# Sheet1.net
KiCad netlist of a schematic drawn in Altium Designer
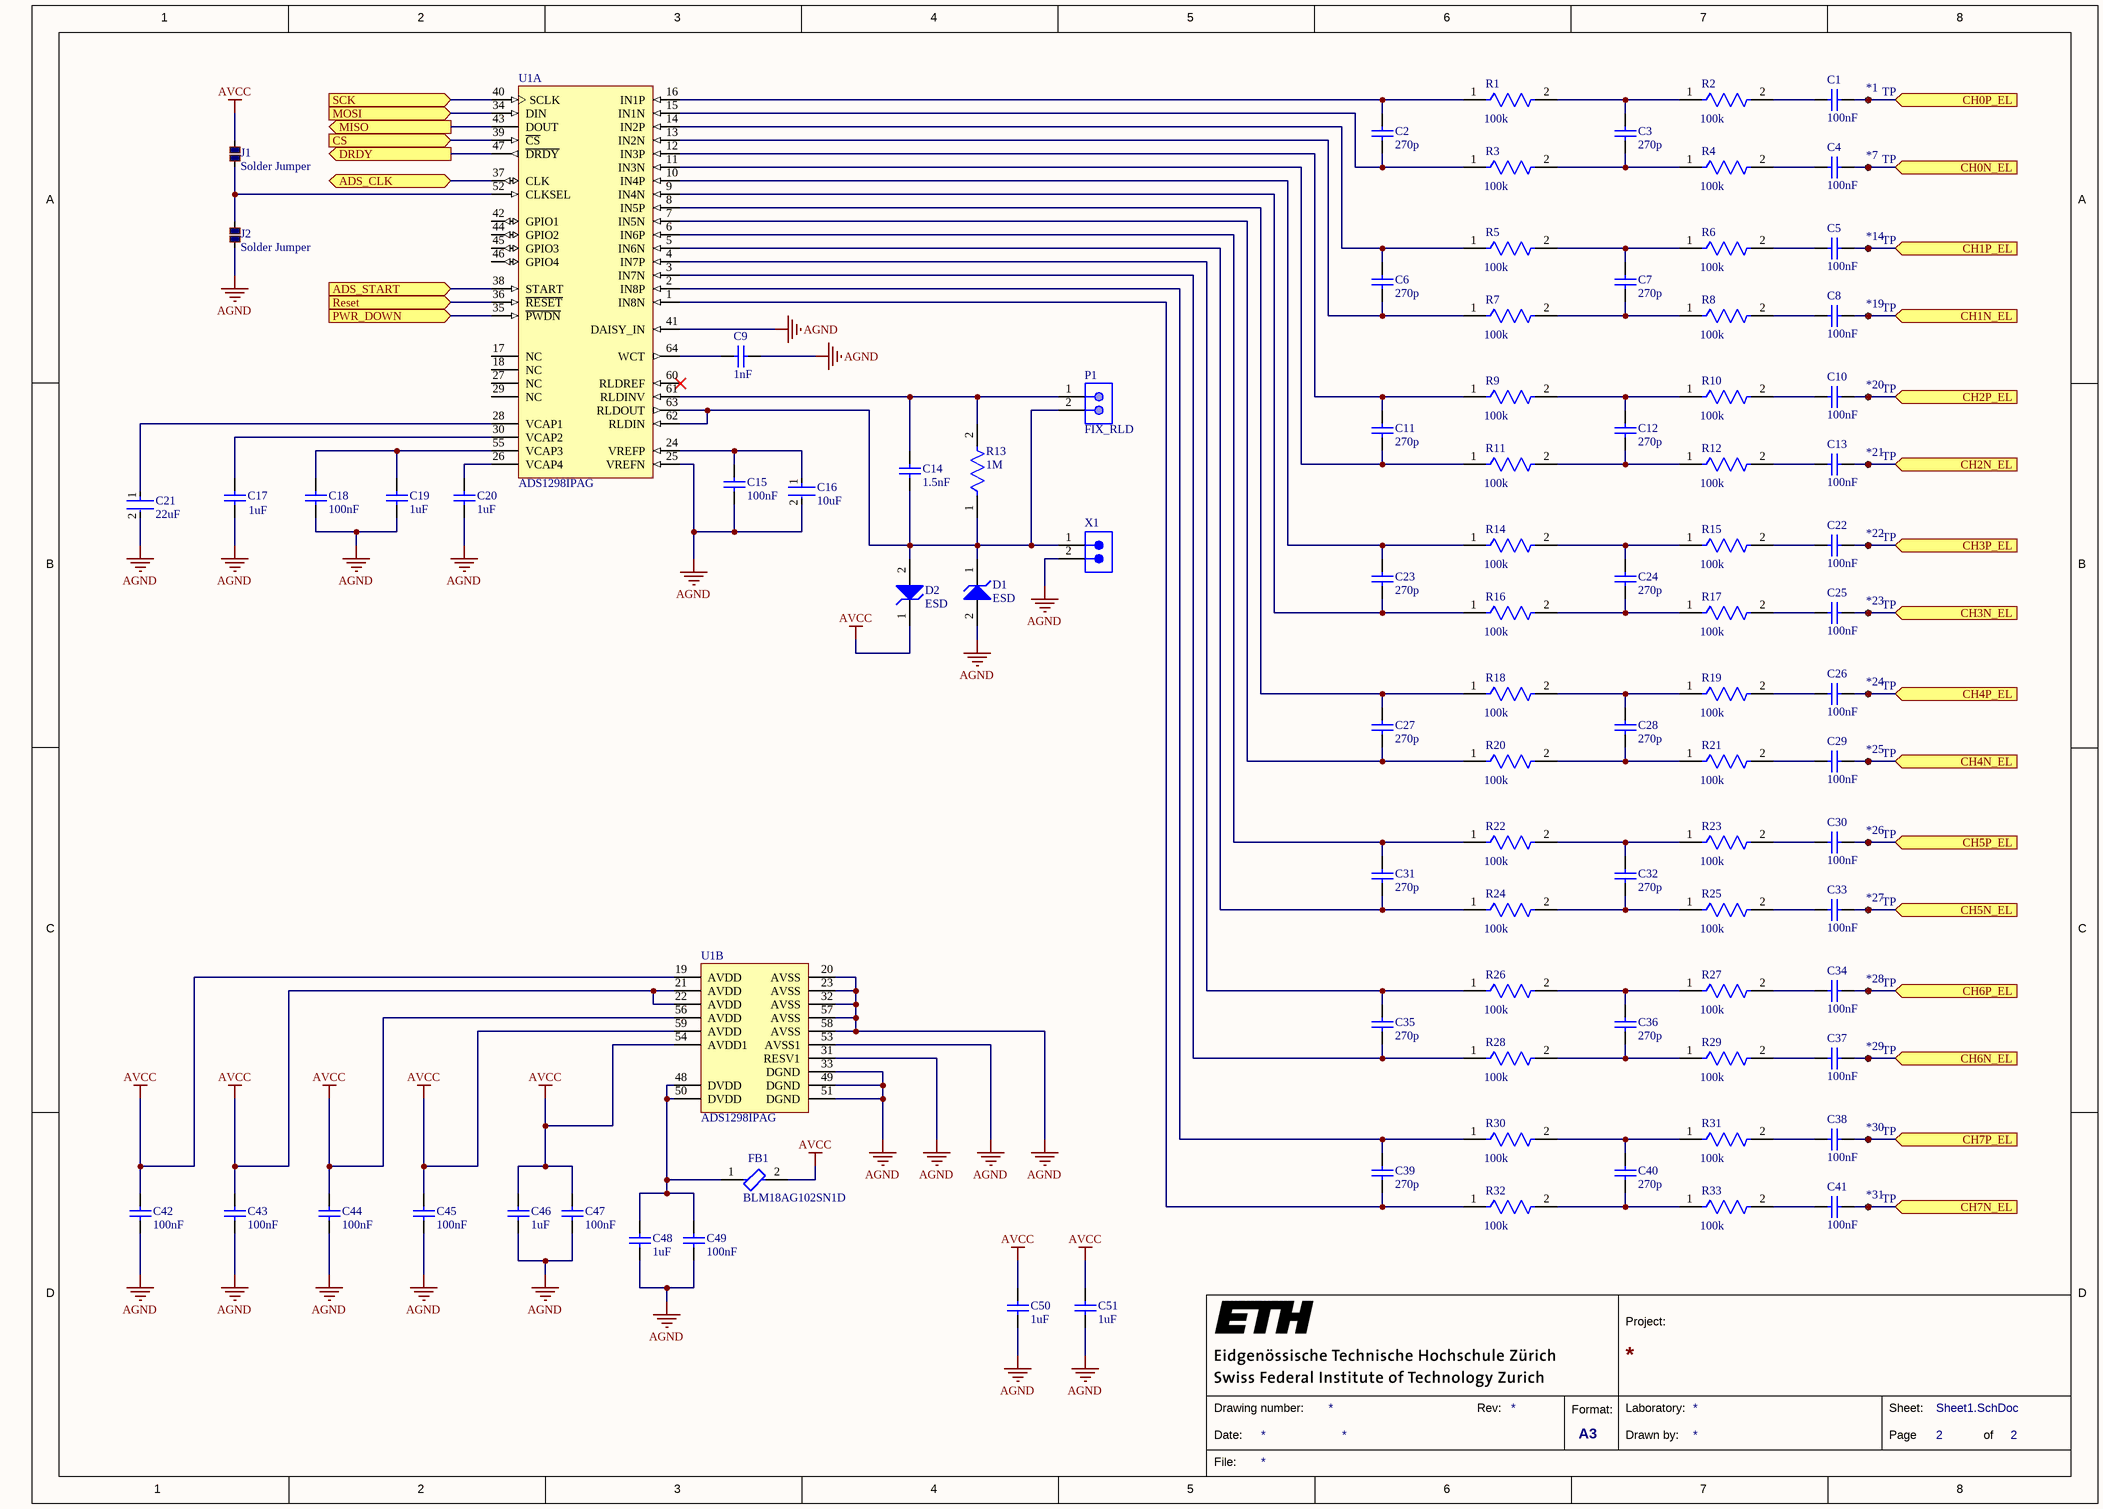
[diagram p0: Sheet1.SchDoc]

(export (version "E")
  (design (tool "Eeschema 10.0.6"))
  (components
    (comp (ref "*1")
      (value "TP")
      (footprint "Pad-1mm")
      (description "1mm SMT Test Pad")
      (libsource (lib "ETHZ Vault") (part "Test Pad"))
    )
    (comp (ref "*7")
      (value "TP")
      (footprint "Pad-1mm")
      (description "1mm SMT Test Pad")
      (libsource (lib "ETHZ Vault") (part "Test Pad"))
    )
    (comp (ref "*14")
      (value "TP")
      (footprint "Pad-1mm")
      (description "1mm SMT Test Pad")
      (libsource (lib "ETHZ Vault") (part "Test Pad"))
    )
    (comp (ref "*19")
      (value "TP")
      (footprint "Pad-1mm")
      (description "1mm SMT Test Pad")
      (libsource (lib "ETHZ Vault") (part "Test Pad"))
    )
    (comp (ref "*20")
      (value "TP")
      (footprint "Pad-1mm")
      (description "1mm SMT Test Pad")
      (libsource (lib "ETHZ Vault") (part "Test Pad"))
    )
    (comp (ref "*21")
      (value "TP")
      (footprint "Pad-1mm")
      (description "1mm SMT Test Pad")
      (libsource (lib "ETHZ Vault") (part "Test Pad"))
    )
    (comp (ref "*22")
      (value "TP")
      (footprint "Pad-1mm")
      (description "1mm SMT Test Pad")
      (libsource (lib "ETHZ Vault") (part "Test Pad"))
    )
    (comp (ref "*23")
      (value "TP")
      (footprint "Pad-1mm")
      (description "1mm SMT Test Pad")
      (libsource (lib "ETHZ Vault") (part "Test Pad"))
    )
    (comp (ref "*24")
      (value "TP")
      (footprint "Pad-1mm")
      (description "1mm SMT Test Pad")
      (libsource (lib "ETHZ Vault") (part "Test Pad"))
    )
    (comp (ref "*25")
      (value "TP")
      (footprint "Pad-1mm")
      (description "1mm SMT Test Pad")
      (libsource (lib "ETHZ Vault") (part "Test Pad"))
    )
    (comp (ref "*26")
      (value "TP")
      (footprint "Pad-1mm")
      (description "1mm SMT Test Pad")
      (libsource (lib "ETHZ Vault") (part "Test Pad"))
    )
    (comp (ref "*27")
      (value "TP")
      (footprint "Pad-1mm")
      (description "1mm SMT Test Pad")
      (libsource (lib "ETHZ Vault") (part "Test Pad"))
    )
    (comp (ref "*28")
      (value "TP")
      (footprint "Pad-1mm")
      (description "1mm SMT Test Pad")
      (libsource (lib "ETHZ Vault") (part "Test Pad"))
    )
    (comp (ref "*29")
      (value "TP")
      (footprint "Pad-1mm")
      (description "1mm SMT Test Pad")
      (libsource (lib "ETHZ Vault") (part "Test Pad"))
    )
    (comp (ref "*30")
      (value "TP")
      (footprint "Pad-1mm")
      (description "1mm SMT Test Pad")
      (libsource (lib "ETHZ Vault") (part "Test Pad"))
    )
    (comp (ref "*31")
      (value "TP")
      (footprint "Pad-1mm")
      (description "1mm SMT Test Pad")
      (libsource (lib "ETHZ Vault") (part "Test Pad"))
    )
    (comp (ref "C1")
      (value "100nF")
      (footprint "CAPC1608X92X38LL15T08")
      (fields (field (name "MANUFACTURER") "Vitramon") (field (name "PART NUMBER") "VJ0603Y104JXJAC"))
      (libsource (lib "Altium Content Vault") (part "CAP"))
    )
    (comp (ref "C2")
      (value "270p")
      (footprint "CAPC1608X90X35NL10T15")
      (fields (field (name "MANUFACTURER") "Murata") (field (name "PART NUMBER") "GCM1885C1H271JA16D"))
      (libsource (lib "Altium Content Vault") (part "CAP"))
    )
    (comp (ref "C3")
      (value "270p")
      (footprint "CAPC1608X90X35NL10T15")
      (fields (field (name "MANUFACTURER") "Murata") (field (name "PART NUMBER") "GCM1885C1H271JA16D"))
      (libsource (lib "Altium Content Vault") (part "CAP"))
    )
    (comp (ref "C4")
      (value "100nF")
      (footprint "CAPC1608X92X38LL15T08")
      (fields (field (name "MANUFACTURER") "Vitramon") (field (name "PART NUMBER") "VJ0603Y104JXJAC"))
      (libsource (lib "Altium Content Vault") (part "CAP"))
    )
    (comp (ref "C5")
      (value "100nF")
      (footprint "CAPC1608X92X38LL15T08")
      (fields (field (name "MANUFACTURER") "Vitramon") (field (name "PART NUMBER") "VJ0603Y104JXJAC"))
      (libsource (lib "Altium Content Vault") (part "CAP"))
    )
    (comp (ref "C6")
      (value "270p")
      (footprint "CAPC1608X90X35NL10T15")
      (fields (field (name "MANUFACTURER") "Murata") (field (name "PART NUMBER") "GCM1885C1H271JA16D"))
      (libsource (lib "Altium Content Vault") (part "CAP"))
    )
    (comp (ref "C7")
      (value "270p")
      (footprint "CAPC1608X90X35NL10T15")
      (fields (field (name "MANUFACTURER") "Murata") (field (name "PART NUMBER") "GCM1885C1H271JA16D"))
      (libsource (lib "Altium Content Vault") (part "CAP"))
    )
    (comp (ref "C8")
      (value "100nF")
      (footprint "CAPC1608X92X38LL15T08")
      (fields (field (name "MANUFACTURER") "Vitramon") (field (name "PART NUMBER") "VJ0603Y104JXJAC"))
      (libsource (lib "Altium Content Vault") (part "CAP"))
    )
    (comp (ref "C9")
      (value "1nF")
      (footprint "CAPC1608X90X35LL10T15")
      (fields (field (name "MANUFACTURER") "Murata") (field (name "PART NUMBER") "GRM1885C1E102JA01D"))
      (libsource (lib "Altium Content Vault") (part "CAP"))
    )
    (comp (ref "C10")
      (value "100nF")
      (footprint "CAPC1608X92X38LL15T08")
      (fields (field (name "MANUFACTURER") "Vitramon") (field (name "PART NUMBER") "VJ0603Y104JXJAC"))
      (libsource (lib "Altium Content Vault") (part "CAP"))
    )
    (comp (ref "C11")
      (value "270p")
      (footprint "CAPC1608X90X35NL10T15")
      (fields (field (name "MANUFACTURER") "Murata") (field (name "PART NUMBER") "GCM1885C1H271JA16D"))
      (libsource (lib "Altium Content Vault") (part "CAP"))
    )
    (comp (ref "C12")
      (value "270p")
      (footprint "CAPC1608X90X35NL10T15")
      (fields (field (name "MANUFACTURER") "Murata") (field (name "PART NUMBER") "GCM1885C1H271JA16D"))
      (libsource (lib "Altium Content Vault") (part "CAP"))
    )
    (comp (ref "C13")
      (value "100nF")
      (footprint "CAPC1608X92X38LL15T08")
      (fields (field (name "MANUFACTURER") "Vitramon") (field (name "PART NUMBER") "VJ0603Y104JXJAC"))
      (libsource (lib "Altium Content Vault") (part "CAP"))
    )
    (comp (ref "C14")
      (value "1.5nF")
      (footprint "CAPC1608X90X35ML10T15")
      (fields (field (name "MANUFACTURER") "Murata") (field (name "PART NUMBER") "GRM188R72A152KA01D"))
      (libsource (lib "Altium Content Vault") (part "CAP"))
    )
    (comp (ref "C15")
      (value "100nF")
      (footprint "CAPC1608X92X38LL15T08")
      (fields (field (name "MANUFACTURER") "Vitramon") (field (name "PART NUMBER") "VJ0603Y104JXJAC"))
      (libsource (lib "Altium Content Vault") (part "CAP"))
    )
    (comp (ref "C16")
      (value "10uF")
      (footprint "FP-GRM188-0_1-e0_2_0_55-IPC_B")
      (description "Chip Multilayer Ceramic Capacitors for General Purpose, 0603, 10uF, X5R, 15%, 20%, 4V")
      (fields (field (name "TOLERANCE") "20%") (field (name "VOLTAGE") "4V"))
      (libsource (lib "Altium Content Vault") (part "02cd4be3c70576c341d710602a673aa"))
    )
    (comp (ref "C17")
      (value "1uF")
      (footprint "CAPC1608X95X40ML15T15")
      (fields (field (name "MANUFACTURER") "Vitramon") (field (name "PART NUMBER") "VJ0603V105ZXQCW1BC"))
      (libsource (lib "Altium Content Vault") (part "CAP"))
    )
    (comp (ref "C18")
      (value "100nF")
      (footprint "CAPC1608X92X38LL15T08")
      (fields (field (name "MANUFACTURER") "Vitramon") (field (name "PART NUMBER") "VJ0603Y104JXJAC"))
      (libsource (lib "Altium Content Vault") (part "CAP"))
    )
    (comp (ref "C19")
      (value "1uF")
      (footprint "CAPC1608X95X40ML15T15")
      (fields (field (name "MANUFACTURER") "Vitramon") (field (name "PART NUMBER") "VJ0603V105ZXQCW1BC"))
      (libsource (lib "Altium Content Vault") (part "CAP"))
    )
    (comp (ref "C20")
      (value "1uF")
      (footprint "CAPC1608X95X40ML15T15")
      (fields (field (name "MANUFACTURER") "Vitramon") (field (name "PART NUMBER") "VJ0603V105ZXQCW1BC"))
      (libsource (lib "Altium Content Vault") (part "CAP"))
    )
    (comp (ref "C21")
      (value "22uF")
      (footprint "FP-CL10-IPC_A")
      (description "Cap Ceramic 22uF 6.3V X5R ±20% Pad SMD 0603 +85°C T/R")
      (fields (field (name "TOLERANCE") "20%"))
      (libsource (lib "Altium Content Vault") (part "b4654b650e69147ec39a6b967a45e02"))
    )
    (comp (ref "C22")
      (value "100nF")
      (footprint "CAPC1608X92X38LL15T08")
      (fields (field (name "MANUFACTURER") "Vitramon") (field (name "PART NUMBER") "VJ0603Y104JXJAC"))
      (libsource (lib "Altium Content Vault") (part "CAP"))
    )
    (comp (ref "C23")
      (value "270p")
      (footprint "CAPC1608X90X35NL10T15")
      (fields (field (name "MANUFACTURER") "Murata") (field (name "PART NUMBER") "GCM1885C1H271JA16D"))
      (libsource (lib "Altium Content Vault") (part "CAP"))
    )
    (comp (ref "C24")
      (value "270p")
      (footprint "CAPC1608X90X35NL10T15")
      (fields (field (name "MANUFACTURER") "Murata") (field (name "PART NUMBER") "GCM1885C1H271JA16D"))
      (libsource (lib "Altium Content Vault") (part "CAP"))
    )
    (comp (ref "C25")
      (value "100nF")
      (footprint "CAPC1608X92X38LL15T08")
      (fields (field (name "MANUFACTURER") "Vitramon") (field (name "PART NUMBER") "VJ0603Y104JXJAC"))
      (libsource (lib "Altium Content Vault") (part "CAP"))
    )
    (comp (ref "C26")
      (value "100nF")
      (footprint "CAPC1608X92X38LL15T08")
      (fields (field (name "MANUFACTURER") "Vitramon") (field (name "PART NUMBER") "VJ0603Y104JXJAC"))
      (libsource (lib "Altium Content Vault") (part "CAP"))
    )
    (comp (ref "C27")
      (value "270p")
      (footprint "CAPC1608X90X35NL10T15")
      (fields (field (name "MANUFACTURER") "Murata") (field (name "PART NUMBER") "GCM1885C1H271JA16D"))
      (libsource (lib "Altium Content Vault") (part "CAP"))
    )
    (comp (ref "C28")
      (value "270p")
      (footprint "CAPC1608X90X35NL10T15")
      (fields (field (name "MANUFACTURER") "Murata") (field (name "PART NUMBER") "GCM1885C1H271JA16D"))
      (libsource (lib "Altium Content Vault") (part "CAP"))
    )
    (comp (ref "C29")
      (value "100nF")
      (footprint "CAPC1608X92X38LL15T08")
      (fields (field (name "MANUFACTURER") "Vitramon") (field (name "PART NUMBER") "VJ0603Y104JXJAC"))
      (libsource (lib "Altium Content Vault") (part "CAP"))
    )
    (comp (ref "C30")
      (value "100nF")
      (footprint "CAPC1608X92X38LL15T08")
      (fields (field (name "MANUFACTURER") "Vitramon") (field (name "PART NUMBER") "VJ0603Y104JXJAC"))
      (libsource (lib "Altium Content Vault") (part "CAP"))
    )
    (comp (ref "C31")
      (value "270p")
      (footprint "CAPC1608X90X35NL10T15")
      (fields (field (name "MANUFACTURER") "Murata") (field (name "PART NUMBER") "GCM1885C1H271JA16D"))
      (libsource (lib "Altium Content Vault") (part "CAP"))
    )
    (comp (ref "C32")
      (value "270p")
      (footprint "CAPC1608X90X35NL10T15")
      (fields (field (name "MANUFACTURER") "Murata") (field (name "PART NUMBER") "GCM1885C1H271JA16D"))
      (libsource (lib "Altium Content Vault") (part "CAP"))
    )
    (comp (ref "C33")
      (value "100nF")
      (footprint "CAPC1608X92X38LL15T08")
      (fields (field (name "MANUFACTURER") "Vitramon") (field (name "PART NUMBER") "VJ0603Y104JXJAC"))
      (libsource (lib "Altium Content Vault") (part "CAP"))
    )
    (comp (ref "C34")
      (value "100nF")
      (footprint "CAPC1608X92X38LL15T08")
      (fields (field (name "MANUFACTURER") "Vitramon") (field (name "PART NUMBER") "VJ0603Y104JXJAC"))
      (libsource (lib "Altium Content Vault") (part "CAP"))
    )
    (comp (ref "C35")
      (value "270p")
      (footprint "CAPC1608X90X35NL10T15")
      (fields (field (name "MANUFACTURER") "Murata") (field (name "PART NUMBER") "GCM1885C1H271JA16D"))
      (libsource (lib "Altium Content Vault") (part "CAP"))
    )
    (comp (ref "C36")
      (value "270p")
      (footprint "CAPC1608X90X35NL10T15")
      (fields (field (name "MANUFACTURER") "Murata") (field (name "PART NUMBER") "GCM1885C1H271JA16D"))
      (libsource (lib "Altium Content Vault") (part "CAP"))
    )
    (comp (ref "C37")
      (value "100nF")
      (footprint "CAPC1608X92X38LL15T08")
      (fields (field (name "MANUFACTURER") "Vitramon") (field (name "PART NUMBER") "VJ0603Y104JXJAC"))
      (libsource (lib "Altium Content Vault") (part "CAP"))
    )
    (comp (ref "C38")
      (value "100nF")
      (footprint "CAPC1608X92X38LL15T08")
      (fields (field (name "MANUFACTURER") "Vitramon") (field (name "PART NUMBER") "VJ0603Y104JXJAC"))
      (libsource (lib "Altium Content Vault") (part "CAP"))
    )
    (comp (ref "C39")
      (value "270p")
      (footprint "CAPC1608X90X35NL10T15")
      (fields (field (name "MANUFACTURER") "Murata") (field (name "PART NUMBER") "GCM1885C1H271JA16D"))
      (libsource (lib "Altium Content Vault") (part "CAP"))
    )
    (comp (ref "C40")
      (value "270p")
      (footprint "CAPC1608X90X35NL10T15")
      (fields (field (name "MANUFACTURER") "Murata") (field (name "PART NUMBER") "GCM1885C1H271JA16D"))
      (libsource (lib "Altium Content Vault") (part "CAP"))
    )
    (comp (ref "C41")
      (value "100nF")
      (footprint "CAPC1608X92X38LL15T08")
      (fields (field (name "MANUFACTURER") "Vitramon") (field (name "PART NUMBER") "VJ0603Y104JXJAC"))
      (libsource (lib "Altium Content Vault") (part "CAP"))
    )
    (comp (ref "C42")
      (value "100nF")
      (footprint "CAPC1608X92X38LL15T08")
      (fields (field (name "MANUFACTURER") "Vitramon") (field (name "PART NUMBER") "VJ0603Y104JXJAC"))
      (libsource (lib "Altium Content Vault") (part "CAP"))
    )
    (comp (ref "C43")
      (value "100nF")
      (footprint "CAPC1608X92X38LL15T08")
      (fields (field (name "MANUFACTURER") "Vitramon") (field (name "PART NUMBER") "VJ0603Y104JXJAC"))
      (libsource (lib "Altium Content Vault") (part "CAP"))
    )
    (comp (ref "C44")
      (value "100nF")
      (footprint "CAPC1608X92X38LL15T08")
      (fields (field (name "MANUFACTURER") "Vitramon") (field (name "PART NUMBER") "VJ0603Y104JXJAC"))
      (libsource (lib "Altium Content Vault") (part "CAP"))
    )
    (comp (ref "C45")
      (value "100nF")
      (footprint "CAPC1608X92X38LL15T08")
      (fields (field (name "MANUFACTURER") "Vitramon") (field (name "PART NUMBER") "VJ0603Y104JXJAC"))
      (libsource (lib "Altium Content Vault") (part "CAP"))
    )
    (comp (ref "C46")
      (value "1uF")
      (footprint "CAPC1608X95X40ML15T15")
      (fields (field (name "MANUFACTURER") "Vitramon") (field (name "PART NUMBER") "VJ0603V105ZXQCW1BC"))
      (libsource (lib "Altium Content Vault") (part "CAP"))
    )
    (comp (ref "C47")
      (value "100nF")
      (footprint "CAPC1608X92X38LL15T08")
      (fields (field (name "MANUFACTURER") "Vitramon") (field (name "PART NUMBER") "VJ0603Y104JXJAC"))
      (libsource (lib "Altium Content Vault") (part "CAP"))
    )
    (comp (ref "C48")
      (value "1uF")
      (footprint "CAPC1608X95X40ML15T15")
      (fields (field (name "MANUFACTURER") "Vitramon") (field (name "PART NUMBER") "VJ0603V105ZXQCW1BC"))
      (libsource (lib "Altium Content Vault") (part "CAP"))
    )
    (comp (ref "C49")
      (value "100nF")
      (footprint "CAPC1608X92X38LL15T08")
      (fields (field (name "MANUFACTURER") "Vitramon") (field (name "PART NUMBER") "VJ0603Y104JXJAC"))
      (libsource (lib "Altium Content Vault") (part "CAP"))
    )
    (comp (ref "C50")
      (value "1uF")
      (footprint "CAPC1608X95X40ML15T15")
      (fields (field (name "MANUFACTURER") "Vitramon") (field (name "PART NUMBER") "VJ0603V105ZXQCW1BC"))
      (libsource (lib "Altium Content Vault") (part "CAP"))
    )
    (comp (ref "C51")
      (value "1uF")
      (footprint "CAPC1608X95X40ML15T15")
      (fields (field (name "MANUFACTURER") "Vitramon") (field (name "PART NUMBER") "VJ0603V105ZXQCW1BC"))
      (libsource (lib "Altium Content Vault") (part "CAP"))
    )
    (comp (ref "D1")
      (value "ESD")
      (footprint "DFN110P160X55-2N")
      (description "TVS DIODE 5V 10.9V 2DFN")
      (libsource (lib "ETHZ Vault") (part "TVS DIODE"))
    )
    (comp (ref "D2")
      (value "ESD")
      (footprint "DFN110P160X55-2N")
      (description "TVS DIODE 5V 10.9V 2DFN")
      (libsource (lib "ETHZ Vault") (part "TVS DIODE"))
    )
    (comp (ref "FB1")
      (value "BLM18AG102SN1D")
      (footprint "FP-BLM18-0_15-t0_8-MFG")
      (description "Chip Ferrite Bead, 0603, 1000Ω @ 100MHz, 0.5Ω, 25%, 450mA")
      (fields (field (name "TOLERANCE") "25%"))
      (libsource (lib "Altium Content Vault") (part "5f30dd21d616792df468990f7003faa"))
    )
    (comp (ref "J1")
      (value "Solder Jumper")
      (footprint "Small Solder Jumper")
      (libsource (lib "ETHZ Vault") (part "Solder Jumper"))
    )
    (comp (ref "J2")
      (value "Solder Jumper")
      (footprint "Small Solder Jumper")
      (libsource (lib "ETHZ Vault") (part "Solder Jumper"))
    )
    (comp (ref "P1")
      (value "FIX_RLD")
      (footprint "SMTC-TSW-102-07-S-S")
      (fields (field (name "MANUFACTURER") "Samtec"))
      (libsource (lib "Altium Content Vault") (part "CN-1P-M-R2"))
    )
    (comp (ref "R1")
      (value "100k")
      (footprint "FP-CRCW0603-e3-IPC_C")
      (description "RES Thick Film, 100kΩ, 1%, 0.1W, 100ppm/°C, 0603")
      (fields (field (name "TOLERANCE") "1%"))
      (libsource (lib "Altium Content Vault") (part "1029c3af85768c4190bb7ad29bc67b5"))
    )
    (comp (ref "R2")
      (value "100k")
      (footprint "FP-CRCW0603-e3-IPC_C")
      (description "RES Thick Film, 100kΩ, 1%, 0.1W, 100ppm/°C, 0603")
      (fields (field (name "TOLERANCE") "1%"))
      (libsource (lib "Altium Content Vault") (part "1029c3af85768c4190bb7ad29bc67b5"))
    )
    (comp (ref "R3")
      (value "100k")
      (footprint "FP-CRCW0603-e3-IPC_C")
      (description "RES Thick Film, 100kΩ, 1%, 0.1W, 100ppm/°C, 0603")
      (fields (field (name "TOLERANCE") "1%"))
      (libsource (lib "Altium Content Vault") (part "1029c3af85768c4190bb7ad29bc67b5"))
    )
    (comp (ref "R4")
      (value "100k")
      (footprint "FP-CRCW0603-e3-IPC_C")
      (description "RES Thick Film, 100kΩ, 1%, 0.1W, 100ppm/°C, 0603")
      (fields (field (name "TOLERANCE") "1%"))
      (libsource (lib "Altium Content Vault") (part "1029c3af85768c4190bb7ad29bc67b5"))
    )
    (comp (ref "R5")
      (value "100k")
      (footprint "FP-CRCW0603-e3-IPC_C")
      (description "RES Thick Film, 100kΩ, 1%, 0.1W, 100ppm/°C, 0603")
      (fields (field (name "TOLERANCE") "1%"))
      (libsource (lib "Altium Content Vault") (part "1029c3af85768c4190bb7ad29bc67b5"))
    )
    (comp (ref "R6")
      (value "100k")
      (footprint "FP-CRCW0603-e3-IPC_C")
      (description "RES Thick Film, 100kΩ, 1%, 0.1W, 100ppm/°C, 0603")
      (fields (field (name "TOLERANCE") "1%"))
      (libsource (lib "Altium Content Vault") (part "1029c3af85768c4190bb7ad29bc67b5"))
    )
    (comp (ref "R7")
      (value "100k")
      (footprint "FP-CRCW0603-e3-IPC_C")
      (description "RES Thick Film, 100kΩ, 1%, 0.1W, 100ppm/°C, 0603")
      (fields (field (name "TOLERANCE") "1%"))
      (libsource (lib "Altium Content Vault") (part "1029c3af85768c4190bb7ad29bc67b5"))
    )
    (comp (ref "R8")
      (value "100k")
      (footprint "FP-CRCW0603-e3-IPC_C")
      (description "RES Thick Film, 100kΩ, 1%, 0.1W, 100ppm/°C, 0603")
      (fields (field (name "TOLERANCE") "1%"))
      (libsource (lib "Altium Content Vault") (part "1029c3af85768c4190bb7ad29bc67b5"))
    )
    (comp (ref "R9")
      (value "100k")
      (footprint "FP-CRCW0603-e3-IPC_C")
      (description "RES Thick Film, 100kΩ, 1%, 0.1W, 100ppm/°C, 0603")
      (fields (field (name "TOLERANCE") "1%"))
      (libsource (lib "Altium Content Vault") (part "1029c3af85768c4190bb7ad29bc67b5"))
    )
    (comp (ref "R10")
      (value "100k")
      (footprint "FP-CRCW0603-e3-IPC_C")
      (description "RES Thick Film, 100kΩ, 1%, 0.1W, 100ppm/°C, 0603")
      (fields (field (name "TOLERANCE") "1%"))
      (libsource (lib "Altium Content Vault") (part "1029c3af85768c4190bb7ad29bc67b5"))
    )
    (comp (ref "R11")
      (value "100k")
      (footprint "FP-CRCW0603-e3-IPC_C")
      (description "RES Thick Film, 100kΩ, 1%, 0.1W, 100ppm/°C, 0603")
      (fields (field (name "TOLERANCE") "1%"))
      (libsource (lib "Altium Content Vault") (part "1029c3af85768c4190bb7ad29bc67b5"))
    )
    (comp (ref "R12")
      (value "100k")
      (footprint "FP-CRCW0603-e3-IPC_C")
      (description "RES Thick Film, 100kΩ, 1%, 0.1W, 100ppm/°C, 0603")
      (fields (field (name "TOLERANCE") "1%"))
      (libsource (lib "Altium Content Vault") (part "1029c3af85768c4190bb7ad29bc67b5"))
    )
    (comp (ref "R13")
      (value "1M")
      (footprint "FP-CRCW0603-e3-MFG")
      (description "RES Thick Film, 1MΩ, 1%, 0.1W, 100ppm/°C, 0603")
      (fields (field (name "TOLERANCE") "1%"))
      (libsource (lib "Altium Content Vault") (part "1029c3af85768c4190bb7ad29bc67b5"))
    )
    (comp (ref "R14")
      (value "100k")
      (footprint "FP-CRCW0603-e3-IPC_C")
      (description "RES Thick Film, 100kΩ, 1%, 0.1W, 100ppm/°C, 0603")
      (fields (field (name "TOLERANCE") "1%"))
      (libsource (lib "Altium Content Vault") (part "1029c3af85768c4190bb7ad29bc67b5"))
    )
    (comp (ref "R15")
      (value "100k")
      (footprint "FP-CRCW0603-e3-IPC_C")
      (description "RES Thick Film, 100kΩ, 1%, 0.1W, 100ppm/°C, 0603")
      (fields (field (name "TOLERANCE") "1%"))
      (libsource (lib "Altium Content Vault") (part "1029c3af85768c4190bb7ad29bc67b5"))
    )
    (comp (ref "R16")
      (value "100k")
      (footprint "FP-CRCW0603-e3-IPC_C")
      (description "RES Thick Film, 100kΩ, 1%, 0.1W, 100ppm/°C, 0603")
      (fields (field (name "TOLERANCE") "1%"))
      (libsource (lib "Altium Content Vault") (part "1029c3af85768c4190bb7ad29bc67b5"))
    )
    (comp (ref "R17")
      (value "100k")
      (footprint "FP-CRCW0603-e3-IPC_C")
      (description "RES Thick Film, 100kΩ, 1%, 0.1W, 100ppm/°C, 0603")
      (fields (field (name "TOLERANCE") "1%"))
      (libsource (lib "Altium Content Vault") (part "1029c3af85768c4190bb7ad29bc67b5"))
    )
    (comp (ref "R18")
      (value "100k")
      (footprint "FP-CRCW0603-e3-IPC_C")
      (description "RES Thick Film, 100kΩ, 1%, 0.1W, 100ppm/°C, 0603")
      (fields (field (name "TOLERANCE") "1%"))
      (libsource (lib "Altium Content Vault") (part "1029c3af85768c4190bb7ad29bc67b5"))
    )
    (comp (ref "R19")
      (value "100k")
      (footprint "FP-CRCW0603-e3-IPC_C")
      (description "RES Thick Film, 100kΩ, 1%, 0.1W, 100ppm/°C, 0603")
      (fields (field (name "TOLERANCE") "1%"))
      (libsource (lib "Altium Content Vault") (part "1029c3af85768c4190bb7ad29bc67b5"))
    )
    (comp (ref "R20")
      (value "100k")
      (footprint "FP-CRCW0603-e3-IPC_C")
      (description "RES Thick Film, 100kΩ, 1%, 0.1W, 100ppm/°C, 0603")
      (fields (field (name "TOLERANCE") "1%"))
      (libsource (lib "Altium Content Vault") (part "1029c3af85768c4190bb7ad29bc67b5"))
    )
    (comp (ref "R21")
      (value "100k")
      (footprint "FP-CRCW0603-e3-IPC_C")
      (description "RES Thick Film, 100kΩ, 1%, 0.1W, 100ppm/°C, 0603")
      (fields (field (name "TOLERANCE") "1%"))
      (libsource (lib "Altium Content Vault") (part "1029c3af85768c4190bb7ad29bc67b5"))
    )
    (comp (ref "R22")
      (value "100k")
      (footprint "FP-CRCW0603-e3-IPC_C")
      (description "RES Thick Film, 100kΩ, 1%, 0.1W, 100ppm/°C, 0603")
      (fields (field (name "TOLERANCE") "1%"))
      (libsource (lib "Altium Content Vault") (part "1029c3af85768c4190bb7ad29bc67b5"))
    )
    (comp (ref "R23")
      (value "100k")
      (footprint "FP-CRCW0603-e3-IPC_C")
      (description "RES Thick Film, 100kΩ, 1%, 0.1W, 100ppm/°C, 0603")
      (fields (field (name "TOLERANCE") "1%"))
      (libsource (lib "Altium Content Vault") (part "1029c3af85768c4190bb7ad29bc67b5"))
    )
    (comp (ref "R24")
      (value "100k")
      (footprint "FP-CRCW0603-e3-IPC_C")
      (description "RES Thick Film, 100kΩ, 1%, 0.1W, 100ppm/°C, 0603")
      (fields (field (name "TOLERANCE") "1%"))
      (libsource (lib "Altium Content Vault") (part "1029c3af85768c4190bb7ad29bc67b5"))
    )
    (comp (ref "R25")
      (value "100k")
      (footprint "FP-CRCW0603-e3-IPC_C")
      (description "RES Thick Film, 100kΩ, 1%, 0.1W, 100ppm/°C, 0603")
      (fields (field (name "TOLERANCE") "1%"))
      (libsource (lib "Altium Content Vault") (part "1029c3af85768c4190bb7ad29bc67b5"))
    )
    (comp (ref "R26")
      (value "100k")
      (footprint "FP-CRCW0603-e3-IPC_C")
      (description "RES Thick Film, 100kΩ, 1%, 0.1W, 100ppm/°C, 0603")
      (fields (field (name "TOLERANCE") "1%"))
      (libsource (lib "Altium Content Vault") (part "1029c3af85768c4190bb7ad29bc67b5"))
    )
    (comp (ref "R27")
      (value "100k")
      (footprint "FP-CRCW0603-e3-IPC_C")
      (description "RES Thick Film, 100kΩ, 1%, 0.1W, 100ppm/°C, 0603")
      (fields (field (name "TOLERANCE") "1%"))
      (libsource (lib "Altium Content Vault") (part "1029c3af85768c4190bb7ad29bc67b5"))
    )
    (comp (ref "R28")
      (value "100k")
      (footprint "FP-CRCW0603-e3-IPC_C")
      (description "RES Thick Film, 100kΩ, 1%, 0.1W, 100ppm/°C, 0603")
      (fields (field (name "TOLERANCE") "1%"))
      (libsource (lib "Altium Content Vault") (part "1029c3af85768c4190bb7ad29bc67b5"))
    )
    (comp (ref "R29")
      (value "100k")
      (footprint "FP-CRCW0603-e3-IPC_C")
      (description "RES Thick Film, 100kΩ, 1%, 0.1W, 100ppm/°C, 0603")
      (fields (field (name "TOLERANCE") "1%"))
      (libsource (lib "Altium Content Vault") (part "1029c3af85768c4190bb7ad29bc67b5"))
    )
    (comp (ref "R30")
      (value "100k")
      (footprint "FP-CRCW0603-e3-IPC_C")
      (description "RES Thick Film, 100kΩ, 1%, 0.1W, 100ppm/°C, 0603")
      (fields (field (name "TOLERANCE") "1%"))
      (libsource (lib "Altium Content Vault") (part "1029c3af85768c4190bb7ad29bc67b5"))
    )
    (comp (ref "R31")
      (value "100k")
      (footprint "FP-CRCW0603-e3-IPC_C")
      (description "RES Thick Film, 100kΩ, 1%, 0.1W, 100ppm/°C, 0603")
      (fields (field (name "TOLERANCE") "1%"))
      (libsource (lib "Altium Content Vault") (part "1029c3af85768c4190bb7ad29bc67b5"))
    )
    (comp (ref "R32")
      (value "100k")
      (footprint "FP-CRCW0603-e3-IPC_C")
      (description "RES Thick Film, 100kΩ, 1%, 0.1W, 100ppm/°C, 0603")
      (fields (field (name "TOLERANCE") "1%"))
      (libsource (lib "Altium Content Vault") (part "1029c3af85768c4190bb7ad29bc67b5"))
    )
    (comp (ref "R33")
      (value "100k")
      (footprint "FP-CRCW0603-e3-IPC_C")
      (description "RES Thick Film, 100kΩ, 1%, 0.1W, 100ppm/°C, 0603")
      (fields (field (name "TOLERANCE") "1%"))
      (libsource (lib "Altium Content Vault") (part "1029c3af85768c4190bb7ad29bc67b5"))
    )
    (comp (ref "U1")
      (value "ADS1298IPAG")
      (footprint "TI-PAG64_L")
      (fields (field (name "MANUFACTURER") "Texas Instruments"))
      (libsource (lib "Altium Content Vault") (part "TI-ADS1298PAG64"))
    )
    (comp (ref "X1")
      (value "43650-0213")
      (footprint "43650-0213")
      (description "Headers & Wire Housings R/A HDR SMT 2P GOLD w/Fitting Nail")
      (fields (field (name "MANUFACTURER") "Molex"))
      (libsource (lib "ETHZ Vault") (part "CON-1x2-Male"))
    )
  )
  (nets
    (net (code "1") (name "/ADS_CLK") (class "Default")
      (node (ref "U1") (pin "37") (pinfunction "CLK_37") (pintype "bidirectional"))
    )
    (net (code "2") (name "/ADS_START") (class "Default")
      (node (ref "U1") (pin "38") (pinfunction "START_38") (pintype "input"))
    )
    (net (code "3") (name "/CH0N_EL") (class "Default")
      (node (ref "*7") (pin "1") (pinfunction "1_1") (pintype "passive"))
      (node (ref "C4") (pin "1") (pinfunction "1_1") (pintype "passive"))
    )
    (net (code "4") (name "/CH0P_EL") (class "Default")
      (node (ref "*1") (pin "1") (pinfunction "1_1") (pintype "passive"))
      (node (ref "C1") (pin "1") (pinfunction "1_1") (pintype "passive"))
    )
    (net (code "5") (name "/CH1N_EL") (class "Default")
      (node (ref "*19") (pin "1") (pinfunction "1_1") (pintype "passive"))
      (node (ref "C8") (pin "1") (pinfunction "1_1") (pintype "passive"))
    )
    (net (code "6") (name "/CH1P_EL") (class "Default")
      (node (ref "*14") (pin "1") (pinfunction "1_1") (pintype "passive"))
      (node (ref "C5") (pin "1") (pinfunction "1_1") (pintype "passive"))
    )
    (net (code "7") (name "/CH2N_EL") (class "Default")
      (node (ref "*21") (pin "1") (pinfunction "1_1") (pintype "passive"))
      (node (ref "C13") (pin "1") (pinfunction "1_1") (pintype "passive"))
    )
    (net (code "8") (name "/CH2P_EL") (class "Default")
      (node (ref "*20") (pin "1") (pinfunction "1_1") (pintype "passive"))
      (node (ref "C10") (pin "1") (pinfunction "1_1") (pintype "passive"))
    )
    (net (code "9") (name "/CH3N_EL") (class "Default")
      (node (ref "*23") (pin "1") (pinfunction "1_1") (pintype "passive"))
      (node (ref "C25") (pin "1") (pinfunction "1_1") (pintype "passive"))
    )
    (net (code "10") (name "/CH3P_EL") (class "Default")
      (node (ref "*22") (pin "1") (pinfunction "1_1") (pintype "passive"))
      (node (ref "C22") (pin "1") (pinfunction "1_1") (pintype "passive"))
    )
    (net (code "11") (name "/CH4N_EL") (class "Default")
      (node (ref "*25") (pin "1") (pinfunction "1_1") (pintype "passive"))
      (node (ref "C29") (pin "1") (pinfunction "1_1") (pintype "passive"))
    )
    (net (code "12") (name "/CH4P_EL") (class "Default")
      (node (ref "*24") (pin "1") (pinfunction "1_1") (pintype "passive"))
      (node (ref "C26") (pin "1") (pinfunction "1_1") (pintype "passive"))
    )
    (net (code "13") (name "/CH5N_EL") (class "Default")
      (node (ref "*27") (pin "1") (pinfunction "1_1") (pintype "passive"))
      (node (ref "C33") (pin "1") (pinfunction "1_1") (pintype "passive"))
    )
    (net (code "14") (name "/CH5P_EL") (class "Default")
      (node (ref "*26") (pin "1") (pinfunction "1_1") (pintype "passive"))
      (node (ref "C30") (pin "1") (pinfunction "1_1") (pintype "passive"))
    )
    (net (code "15") (name "/CH6N_EL") (class "Default")
      (node (ref "*29") (pin "1") (pinfunction "1_1") (pintype "passive"))
      (node (ref "C37") (pin "1") (pinfunction "1_1") (pintype "passive"))
    )
    (net (code "16") (name "/CH6P_EL") (class "Default")
      (node (ref "*28") (pin "1") (pinfunction "1_1") (pintype "passive"))
      (node (ref "C34") (pin "1") (pinfunction "1_1") (pintype "passive"))
    )
    (net (code "17") (name "/CH7N_EL") (class "Default")
      (node (ref "*31") (pin "1") (pinfunction "1_1") (pintype "passive"))
      (node (ref "C41") (pin "1") (pinfunction "1_1") (pintype "passive"))
    )
    (net (code "18") (name "/CH7P_EL") (class "Default")
      (node (ref "*30") (pin "1") (pinfunction "1_1") (pintype "passive"))
      (node (ref "C38") (pin "1") (pinfunction "1_1") (pintype "passive"))
    )
    (net (code "19") (name "/CS") (class "Default")
      (node (ref "U1") (pin "39") (pinfunction "~{CS}_39") (pintype "input"))
    )
    (net (code "20") (name "/DRDY") (class "Default")
      (node (ref "U1") (pin "47") (pinfunction "~{DRDY}_47") (pintype "output"))
    )
    (net (code "21") (name "/MISO") (class "Default")
      (node (ref "U1") (pin "43") (pinfunction "DOUT_43") (pintype "tri_state"))
    )
    (net (code "22") (name "/MOSI") (class "Default")
      (node (ref "U1") (pin "34") (pinfunction "DIN_34") (pintype "input"))
    )
    (net (code "23") (name "/PWR_DOWN") (class "Default")
      (node (ref "U1") (pin "35") (pinfunction "~{PWDN}_35") (pintype "input"))
    )
    (net (code "24") (name "/Reset") (class "Default")
      (node (ref "U1") (pin "36") (pinfunction "~{RESET}_36") (pintype "input"))
    )
    (net (code "25") (name "/SCK") (class "Default")
      (node (ref "U1") (pin "40") (pinfunction "SCLK_40") (pintype "input"))
    )
    (net (code "26") (name "AGND") (class "Default")
      (node (ref "C15") (pin "1") (pinfunction "1_1") (pintype "passive"))
      (node (ref "C16") (pin "2") (pinfunction "2_2") (pintype "passive"))
      (node (ref "C17") (pin "1") (pinfunction "1_1") (pintype "passive"))
      (node (ref "C18") (pin "2") (pinfunction "2_2") (pintype "passive"))
      (node (ref "C19") (pin "1") (pinfunction "1_1") (pintype "passive"))
      (node (ref "C20") (pin "1") (pinfunction "1_1") (pintype "passive"))
      (node (ref "C21") (pin "2") (pinfunction "2_2") (pintype "passive"))
      (node (ref "C42") (pin "1") (pinfunction "1_1") (pintype "passive"))
      (node (ref "C43") (pin "1") (pinfunction "1_1") (pintype "passive"))
      (node (ref "C44") (pin "1") (pinfunction "1_1") (pintype "passive"))
      (node (ref "C45") (pin "1") (pinfunction "1_1") (pintype "passive"))
      (node (ref "C46") (pin "1") (pinfunction "1_1") (pintype "passive"))
      (node (ref "C47") (pin "1") (pinfunction "1_1") (pintype "passive"))
      (node (ref "C48") (pin "1") (pinfunction "1_1") (pintype "passive"))
      (node (ref "C49") (pin "1") (pinfunction "1_1") (pintype "passive"))
      (node (ref "C50") (pin "1") (pinfunction "1_1") (pintype "passive"))
      (node (ref "C51") (pin "1") (pinfunction "1_1") (pintype "passive"))
      (node (ref "C9") (pin "1") (pinfunction "1_1") (pintype "passive"))
      (node (ref "D1") (pin "2") (pinfunction "2_2") (pintype "passive"))
      (node (ref "J2") (pin "1") (pintype "passive"))
      (node (ref "U1") (pin "20") (pinfunction "AVSS_20") (pintype "power_in"))
      (node (ref "U1") (pin "23") (pinfunction "AVSS_23") (pintype "power_in"))
      (node (ref "U1") (pin "25") (pinfunction "VREFN_25") (pintype "input"))
      (node (ref "U1") (pin "31") (pinfunction "RESV1_31") (pintype "power_in"))
      (node (ref "U1") (pin "32") (pinfunction "AVSS_32") (pintype "power_in"))
      (node (ref "U1") (pin "33") (pinfunction "DGND_33") (pintype "power_in"))
      (node (ref "U1") (pin "41") (pinfunction "DAISY_IN_41") (pintype "input"))
      (node (ref "U1") (pin "49") (pinfunction "DGND_49") (pintype "power_in"))
      (node (ref "U1") (pin "51") (pinfunction "DGND_51") (pintype "power_in"))
      (node (ref "U1") (pin "53") (pinfunction "AVSS1_53") (pintype "power_in"))
      (node (ref "U1") (pin "57") (pinfunction "AVSS_57") (pintype "power_in"))
      (node (ref "U1") (pin "58") (pinfunction "AVSS_58") (pintype "power_in"))
      (node (ref "X1") (pin "2") (pinfunction "2_2") (pintype "passive"))
    )
    (net (code "27") (name "AVCC") (class "Default")
      (node (ref "C42") (pin "2") (pinfunction "2_2") (pintype "passive"))
      (node (ref "C43") (pin "2") (pinfunction "2_2") (pintype "passive"))
      (node (ref "C44") (pin "2") (pinfunction "2_2") (pintype "passive"))
      (node (ref "C45") (pin "2") (pinfunction "2_2") (pintype "passive"))
      (node (ref "C46") (pin "2") (pinfunction "2_2") (pintype "passive"))
      (node (ref "C47") (pin "2") (pinfunction "2_2") (pintype "passive"))
      (node (ref "C50") (pin "2") (pinfunction "2_2") (pintype "passive"))
      (node (ref "C51") (pin "2") (pinfunction "2_2") (pintype "passive"))
      (node (ref "D2") (pin "1") (pinfunction "1_1") (pintype "passive"))
      (node (ref "FB1") (pin "2") (pinfunction "2_2") (pintype "passive"))
      (node (ref "J1") (pin "2") (pintype "passive"))
      (node (ref "U1") (pin "19") (pinfunction "AVDD_19") (pintype "power_in"))
      (node (ref "U1") (pin "21") (pinfunction "AVDD_21") (pintype "power_in"))
      (node (ref "U1") (pin "22") (pinfunction "AVDD_22") (pintype "power_in"))
      (node (ref "U1") (pin "54") (pinfunction "AVDD1_54") (pintype "power_in"))
      (node (ref "U1") (pin "56") (pinfunction "AVDD_56") (pintype "power_in"))
      (node (ref "U1") (pin "59") (pinfunction "AVDD_59") (pintype "power_in"))
    )
    (net (code "28") (name "Net-(C1-Pad2)") (class "Default")
      (node (ref "C1") (pin "2") (pinfunction "2_2") (pintype "passive"))
      (node (ref "R2") (pin "2") (pinfunction "2_2") (pintype "passive"))
    )
    (net (code "29") (name "Net-(C3-Pad1)") (class "Default")
      (node (ref "C3") (pin "1") (pinfunction "1_1") (pintype "passive"))
      (node (ref "R3") (pin "2") (pinfunction "2_2") (pintype "passive"))
      (node (ref "R4") (pin "1") (pinfunction "1_1") (pintype "passive"))
    )
    (net (code "30") (name "Net-(C3-Pad2)") (class "Default")
      (node (ref "C3") (pin "2") (pinfunction "2_2") (pintype "passive"))
      (node (ref "R1") (pin "2") (pinfunction "2_2") (pintype "passive"))
      (node (ref "R2") (pin "1") (pinfunction "1_1") (pintype "passive"))
    )
    (net (code "31") (name "Net-(C4-Pad2)") (class "Default")
      (node (ref "C4") (pin "2") (pinfunction "2_2") (pintype "passive"))
      (node (ref "R4") (pin "2") (pinfunction "2_2") (pintype "passive"))
    )
    (net (code "32") (name "Net-(C5-Pad2)") (class "Default")
      (node (ref "C5") (pin "2") (pinfunction "2_2") (pintype "passive"))
      (node (ref "R6") (pin "2") (pinfunction "2_2") (pintype "passive"))
    )
    (net (code "33") (name "Net-(C7-Pad1)") (class "Default")
      (node (ref "C7") (pin "1") (pinfunction "1_1") (pintype "passive"))
      (node (ref "R7") (pin "2") (pinfunction "2_2") (pintype "passive"))
      (node (ref "R8") (pin "1") (pinfunction "1_1") (pintype "passive"))
    )
    (net (code "34") (name "Net-(C7-Pad2)") (class "Default")
      (node (ref "C7") (pin "2") (pinfunction "2_2") (pintype "passive"))
      (node (ref "R5") (pin "2") (pinfunction "2_2") (pintype "passive"))
      (node (ref "R6") (pin "1") (pinfunction "1_1") (pintype "passive"))
    )
    (net (code "35") (name "Net-(C8-Pad2)") (class "Default")
      (node (ref "C8") (pin "2") (pinfunction "2_2") (pintype "passive"))
      (node (ref "R8") (pin "2") (pinfunction "2_2") (pintype "passive"))
    )
    (net (code "36") (name "Net-(C10-Pad2)") (class "Default")
      (node (ref "C10") (pin "2") (pinfunction "2_2") (pintype "passive"))
      (node (ref "R10") (pin "2") (pinfunction "2_2") (pintype "passive"))
    )
    (net (code "37") (name "Net-(C12-Pad1)") (class "Default")
      (node (ref "C12") (pin "1") (pinfunction "1_1") (pintype "passive"))
      (node (ref "R11") (pin "2") (pinfunction "2_2") (pintype "passive"))
      (node (ref "R12") (pin "1") (pinfunction "1_1") (pintype "passive"))
    )
    (net (code "38") (name "Net-(C12-Pad2)") (class "Default")
      (node (ref "C12") (pin "2") (pinfunction "2_2") (pintype "passive"))
      (node (ref "R10") (pin "1") (pinfunction "1_1") (pintype "passive"))
      (node (ref "R9") (pin "2") (pinfunction "2_2") (pintype "passive"))
    )
    (net (code "39") (name "Net-(C13-Pad2)") (class "Default")
      (node (ref "C13") (pin "2") (pinfunction "2_2") (pintype "passive"))
      (node (ref "R12") (pin "2") (pinfunction "2_2") (pintype "passive"))
    )
    (net (code "40") (name "Net-(C22-Pad2)") (class "Default")
      (node (ref "C22") (pin "2") (pinfunction "2_2") (pintype "passive"))
      (node (ref "R15") (pin "2") (pinfunction "2_2") (pintype "passive"))
    )
    (net (code "41") (name "Net-(C24-Pad1)") (class "Default")
      (node (ref "C24") (pin "1") (pinfunction "1_1") (pintype "passive"))
      (node (ref "R16") (pin "2") (pinfunction "2_2") (pintype "passive"))
      (node (ref "R17") (pin "1") (pinfunction "1_1") (pintype "passive"))
    )
    (net (code "42") (name "Net-(C24-Pad2)") (class "Default")
      (node (ref "C24") (pin "2") (pinfunction "2_2") (pintype "passive"))
      (node (ref "R14") (pin "2") (pinfunction "2_2") (pintype "passive"))
      (node (ref "R15") (pin "1") (pinfunction "1_1") (pintype "passive"))
    )
    (net (code "43") (name "Net-(C25-Pad2)") (class "Default")
      (node (ref "C25") (pin "2") (pinfunction "2_2") (pintype "passive"))
      (node (ref "R17") (pin "2") (pinfunction "2_2") (pintype "passive"))
    )
    (net (code "44") (name "Net-(C26-Pad2)") (class "Default")
      (node (ref "C26") (pin "2") (pinfunction "2_2") (pintype "passive"))
      (node (ref "R19") (pin "2") (pinfunction "2_2") (pintype "passive"))
    )
    (net (code "45") (name "Net-(C28-Pad1)") (class "Default")
      (node (ref "C28") (pin "1") (pinfunction "1_1") (pintype "passive"))
      (node (ref "R20") (pin "2") (pinfunction "2_2") (pintype "passive"))
      (node (ref "R21") (pin "1") (pinfunction "1_1") (pintype "passive"))
    )
    (net (code "46") (name "Net-(C28-Pad2)") (class "Default")
      (node (ref "C28") (pin "2") (pinfunction "2_2") (pintype "passive"))
      (node (ref "R18") (pin "2") (pinfunction "2_2") (pintype "passive"))
      (node (ref "R19") (pin "1") (pinfunction "1_1") (pintype "passive"))
    )
    (net (code "47") (name "Net-(C29-Pad2)") (class "Default")
      (node (ref "C29") (pin "2") (pinfunction "2_2") (pintype "passive"))
      (node (ref "R21") (pin "2") (pinfunction "2_2") (pintype "passive"))
    )
    (net (code "48") (name "Net-(C30-Pad2)") (class "Default")
      (node (ref "C30") (pin "2") (pinfunction "2_2") (pintype "passive"))
      (node (ref "R23") (pin "2") (pinfunction "2_2") (pintype "passive"))
    )
    (net (code "49") (name "Net-(C32-Pad1)") (class "Default")
      (node (ref "C32") (pin "1") (pinfunction "1_1") (pintype "passive"))
      (node (ref "R24") (pin "2") (pinfunction "2_2") (pintype "passive"))
      (node (ref "R25") (pin "1") (pinfunction "1_1") (pintype "passive"))
    )
    (net (code "50") (name "Net-(C32-Pad2)") (class "Default")
      (node (ref "C32") (pin "2") (pinfunction "2_2") (pintype "passive"))
      (node (ref "R22") (pin "2") (pinfunction "2_2") (pintype "passive"))
      (node (ref "R23") (pin "1") (pinfunction "1_1") (pintype "passive"))
    )
    (net (code "51") (name "Net-(C33-Pad2)") (class "Default")
      (node (ref "C33") (pin "2") (pinfunction "2_2") (pintype "passive"))
      (node (ref "R25") (pin "2") (pinfunction "2_2") (pintype "passive"))
    )
    (net (code "52") (name "Net-(C34-Pad2)") (class "Default")
      (node (ref "C34") (pin "2") (pinfunction "2_2") (pintype "passive"))
      (node (ref "R27") (pin "2") (pinfunction "2_2") (pintype "passive"))
    )
    (net (code "53") (name "Net-(C36-Pad1)") (class "Default")
      (node (ref "C36") (pin "1") (pinfunction "1_1") (pintype "passive"))
      (node (ref "R28") (pin "2") (pinfunction "2_2") (pintype "passive"))
      (node (ref "R29") (pin "1") (pinfunction "1_1") (pintype "passive"))
    )
    (net (code "54") (name "Net-(C36-Pad2)") (class "Default")
      (node (ref "C36") (pin "2") (pinfunction "2_2") (pintype "passive"))
      (node (ref "R26") (pin "2") (pinfunction "2_2") (pintype "passive"))
      (node (ref "R27") (pin "1") (pinfunction "1_1") (pintype "passive"))
    )
    (net (code "55") (name "Net-(C37-Pad2)") (class "Default")
      (node (ref "C37") (pin "2") (pinfunction "2_2") (pintype "passive"))
      (node (ref "R29") (pin "2") (pinfunction "2_2") (pintype "passive"))
    )
    (net (code "56") (name "Net-(C38-Pad2)") (class "Default")
      (node (ref "C38") (pin "2") (pinfunction "2_2") (pintype "passive"))
      (node (ref "R31") (pin "2") (pinfunction "2_2") (pintype "passive"))
    )
    (net (code "57") (name "Net-(C40-Pad1)") (class "Default")
      (node (ref "C40") (pin "1") (pinfunction "1_1") (pintype "passive"))
      (node (ref "R32") (pin "2") (pinfunction "2_2") (pintype "passive"))
      (node (ref "R33") (pin "1") (pinfunction "1_1") (pintype "passive"))
    )
    (net (code "58") (name "Net-(C40-Pad2)") (class "Default")
      (node (ref "C40") (pin "2") (pinfunction "2_2") (pintype "passive"))
      (node (ref "R30") (pin "2") (pinfunction "2_2") (pintype "passive"))
      (node (ref "R31") (pin "1") (pinfunction "1_1") (pintype "passive"))
    )
    (net (code "59") (name "Net-(C41-Pad2)") (class "Default")
      (node (ref "C41") (pin "2") (pinfunction "2_2") (pintype "passive"))
      (node (ref "R33") (pin "2") (pinfunction "2_2") (pintype "passive"))
    )
    (net (code "60") (name "Net-(C48-Pad2)") (class "Default")
      (node (ref "C48") (pin "2") (pinfunction "2_2") (pintype "passive"))
      (node (ref "C49") (pin "2") (pinfunction "2_2") (pintype "passive"))
      (node (ref "FB1") (pin "1") (pinfunction "1_1") (pintype "passive"))
      (node (ref "U1") (pin "48") (pinfunction "DVDD_48") (pintype "power_in"))
      (node (ref "U1") (pin "50") (pinfunction "DVDD_50") (pintype "power_in"))
    )
    (net (code "61") (name "Net-(U1A-CLKSEL)") (class "Default")
      (node (ref "J1") (pin "1") (pintype "passive"))
      (node (ref "J2") (pin "2") (pintype "passive"))
      (node (ref "U1") (pin "52") (pinfunction "CLKSEL_52") (pintype "input"))
    )
    (net (code "62") (name "Net-(U1A-IN1N)") (class "Default")
      (node (ref "C2") (pin "1") (pinfunction "1_1") (pintype "passive"))
      (node (ref "R3") (pin "1") (pinfunction "1_1") (pintype "passive"))
      (node (ref "U1") (pin "15") (pinfunction "IN1N_15") (pintype "input"))
    )
    (net (code "63") (name "Net-(U1A-IN1P)") (class "Default")
      (node (ref "C2") (pin "2") (pinfunction "2_2") (pintype "passive"))
      (node (ref "R1") (pin "1") (pinfunction "1_1") (pintype "passive"))
      (node (ref "U1") (pin "16") (pinfunction "IN1P_16") (pintype "input"))
    )
    (net (code "64") (name "Net-(U1A-IN2N)") (class "Default")
      (node (ref "C6") (pin "1") (pinfunction "1_1") (pintype "passive"))
      (node (ref "R7") (pin "1") (pinfunction "1_1") (pintype "passive"))
      (node (ref "U1") (pin "13") (pinfunction "IN2N_13") (pintype "input"))
    )
    (net (code "65") (name "Net-(U1A-IN2P)") (class "Default")
      (node (ref "C6") (pin "2") (pinfunction "2_2") (pintype "passive"))
      (node (ref "R5") (pin "1") (pinfunction "1_1") (pintype "passive"))
      (node (ref "U1") (pin "14") (pinfunction "IN2P_14") (pintype "input"))
    )
    (net (code "66") (name "Net-(U1A-IN3N)") (class "Default")
      (node (ref "C11") (pin "1") (pinfunction "1_1") (pintype "passive"))
      (node (ref "R11") (pin "1") (pinfunction "1_1") (pintype "passive"))
      (node (ref "U1") (pin "11") (pinfunction "IN3N_11") (pintype "input"))
    )
    (net (code "67") (name "Net-(U1A-IN3P)") (class "Default")
      (node (ref "C11") (pin "2") (pinfunction "2_2") (pintype "passive"))
      (node (ref "R9") (pin "1") (pinfunction "1_1") (pintype "passive"))
      (node (ref "U1") (pin "12") (pinfunction "IN3P_12") (pintype "input"))
    )
    (net (code "68") (name "Net-(U1A-IN4N)") (class "Default")
      (node (ref "C23") (pin "1") (pinfunction "1_1") (pintype "passive"))
      (node (ref "R16") (pin "1") (pinfunction "1_1") (pintype "passive"))
      (node (ref "U1") (pin "9") (pinfunction "IN4N_9") (pintype "input"))
    )
    (net (code "69") (name "Net-(U1A-IN4P)") (class "Default")
      (node (ref "C23") (pin "2") (pinfunction "2_2") (pintype "passive"))
      (node (ref "R14") (pin "1") (pinfunction "1_1") (pintype "passive"))
      (node (ref "U1") (pin "10") (pinfunction "IN4P_10") (pintype "input"))
    )
    (net (code "70") (name "Net-(U1A-IN5N)") (class "Default")
      (node (ref "C27") (pin "1") (pinfunction "1_1") (pintype "passive"))
      (node (ref "R20") (pin "1") (pinfunction "1_1") (pintype "passive"))
      (node (ref "U1") (pin "7") (pinfunction "IN5N_7") (pintype "input"))
    )
    (net (code "71") (name "Net-(U1A-IN5P)") (class "Default")
      (node (ref "C27") (pin "2") (pinfunction "2_2") (pintype "passive"))
      (node (ref "R18") (pin "1") (pinfunction "1_1") (pintype "passive"))
      (node (ref "U1") (pin "8") (pinfunction "IN5P_8") (pintype "input"))
    )
    (net (code "72") (name "Net-(U1A-IN6N)") (class "Default")
      (node (ref "C31") (pin "1") (pinfunction "1_1") (pintype "passive"))
      (node (ref "R24") (pin "1") (pinfunction "1_1") (pintype "passive"))
      (node (ref "U1") (pin "5") (pinfunction "IN6N_5") (pintype "input"))
    )
    (net (code "73") (name "Net-(U1A-IN6P)") (class "Default")
      (node (ref "C31") (pin "2") (pinfunction "2_2") (pintype "passive"))
      (node (ref "R22") (pin "1") (pinfunction "1_1") (pintype "passive"))
      (node (ref "U1") (pin "6") (pinfunction "IN6P_6") (pintype "input"))
    )
    (net (code "74") (name "Net-(U1A-IN7N)") (class "Default")
      (node (ref "C35") (pin "1") (pinfunction "1_1") (pintype "passive"))
      (node (ref "R28") (pin "1") (pinfunction "1_1") (pintype "passive"))
      (node (ref "U1") (pin "3") (pinfunction "IN7N_3") (pintype "input"))
    )
    (net (code "75") (name "Net-(U1A-IN7P)") (class "Default")
      (node (ref "C35") (pin "2") (pinfunction "2_2") (pintype "passive"))
      (node (ref "R26") (pin "1") (pinfunction "1_1") (pintype "passive"))
      (node (ref "U1") (pin "4") (pinfunction "IN7P_4") (pintype "input"))
    )
    (net (code "76") (name "Net-(U1A-IN8N)") (class "Default")
      (node (ref "C39") (pin "1") (pinfunction "1_1") (pintype "passive"))
      (node (ref "R32") (pin "1") (pinfunction "1_1") (pintype "passive"))
      (node (ref "U1") (pin "1") (pinfunction "IN8N_1") (pintype "input"))
    )
    (net (code "77") (name "Net-(U1A-IN8P)") (class "Default")
      (node (ref "C39") (pin "2") (pinfunction "2_2") (pintype "passive"))
      (node (ref "R30") (pin "1") (pinfunction "1_1") (pintype "passive"))
      (node (ref "U1") (pin "2") (pinfunction "IN8P_2") (pintype "input"))
    )
    (net (code "78") (name "Net-(U1A-RLDIN)") (class "Default")
      (node (ref "C14") (pin "1") (pinfunction "1_1") (pintype "passive"))
      (node (ref "D1") (pin "1") (pinfunction "1_1") (pintype "passive"))
      (node (ref "D2") (pin "2") (pinfunction "2_2") (pintype "passive"))
      (node (ref "P1") (pin "2") (pinfunction "2_2") (pintype "passive"))
      (node (ref "R13") (pin "1") (pinfunction "1_1") (pintype "passive"))
      (node (ref "U1") (pin "62") (pinfunction "RLDIN_62") (pintype "input"))
      (node (ref "U1") (pin "63") (pinfunction "RLDOUT_63") (pintype "output"))
      (node (ref "X1") (pin "1") (pinfunction "1_1") (pintype "passive"))
    )
    (net (code "79") (name "Net-(U1A-RLDINV)") (class "Default")
      (node (ref "C14") (pin "2") (pinfunction "2_2") (pintype "passive"))
      (node (ref "P1") (pin "1") (pinfunction "1_1") (pintype "passive"))
      (node (ref "R13") (pin "2") (pinfunction "2_2") (pintype "passive"))
      (node (ref "U1") (pin "61") (pinfunction "RLDINV_61") (pintype "input"))
    )
    (net (code "80") (name "Net-(U1A-VCAP1)") (class "Default")
      (node (ref "C21") (pin "1") (pinfunction "1_1") (pintype "passive"))
      (node (ref "U1") (pin "28") (pinfunction "VCAP1_28") (pintype "passive"))
    )
    (net (code "81") (name "Net-(U1A-VCAP2)") (class "Default")
      (node (ref "C17") (pin "2") (pinfunction "2_2") (pintype "passive"))
      (node (ref "U1") (pin "30") (pinfunction "VCAP2_30") (pintype "passive"))
    )
    (net (code "82") (name "Net-(U1A-VCAP3)") (class "Default")
      (node (ref "C18") (pin "1") (pinfunction "1_1") (pintype "passive"))
      (node (ref "C19") (pin "2") (pinfunction "2_2") (pintype "passive"))
      (node (ref "U1") (pin "55") (pinfunction "VCAP3_55") (pintype "passive"))
    )
    (net (code "83") (name "Net-(U1A-VCAP4)") (class "Default")
      (node (ref "C20") (pin "2") (pinfunction "2_2") (pintype "passive"))
      (node (ref "U1") (pin "26") (pinfunction "VCAP4_26") (pintype "passive"))
    )
    (net (code "84") (name "Net-(U1A-VREFP)") (class "Default")
      (node (ref "C15") (pin "2") (pinfunction "2_2") (pintype "passive"))
      (node (ref "C16") (pin "1") (pinfunction "1_1") (pintype "passive"))
      (node (ref "U1") (pin "24") (pinfunction "VREFP_24") (pintype "input"))
    )
    (net (code "85") (name "Net-(U1A-WCT)") (class "Default")
      (node (ref "C9") (pin "2") (pinfunction "2_2") (pintype "passive"))
      (node (ref "U1") (pin "64") (pinfunction "WCT_64") (pintype "output"))
    )
    (net (code "86") (name "unconnected-(U1A-GPIO1-Pad42)") (class "Default")
      (node (ref "U1") (pin "42") (pinfunction "GPIO1_42") (pintype "bidirectional"))
    )
    (net (code "87") (name "unconnected-(U1A-GPIO2-Pad44)") (class "Default")
      (node (ref "U1") (pin "44") (pinfunction "GPIO2_44") (pintype "bidirectional"))
    )
    (net (code "88") (name "unconnected-(U1A-GPIO3-Pad45)") (class "Default")
      (node (ref "U1") (pin "45") (pinfunction "GPIO3_45") (pintype "bidirectional"))
    )
    (net (code "89") (name "unconnected-(U1A-GPIO4-Pad46)") (class "Default")
      (node (ref "U1") (pin "46") (pinfunction "GPIO4_46") (pintype "bidirectional"))
    )
    (net (code "90") (name "unconnected-(U1A-NC-Pad17)") (class "Default")
      (node (ref "U1") (pin "17") (pinfunction "NC_17") (pintype "passive"))
    )
    (net (code "91") (name "unconnected-(U1A-NC-Pad18)") (class "Default")
      (node (ref "U1") (pin "18") (pinfunction "NC_18") (pintype "passive"))
    )
    (net (code "92") (name "unconnected-(U1A-NC-Pad27)") (class "Default")
      (node (ref "U1") (pin "27") (pinfunction "NC_27") (pintype "passive"))
    )
    (net (code "93") (name "unconnected-(U1A-NC-Pad29)") (class "Default")
      (node (ref "U1") (pin "29") (pinfunction "NC_29") (pintype "passive"))
    )
    (net (code "94") (name "unconnected-(U1A-RLDREF-Pad60)") (class "Default")
      (node (ref "U1") (pin "60") (pinfunction "RLDREF_60") (pintype "input+no_connect"))
    )
  )
)
